# cape.net
KiCad netlist of a schematic drawn in EAGLE
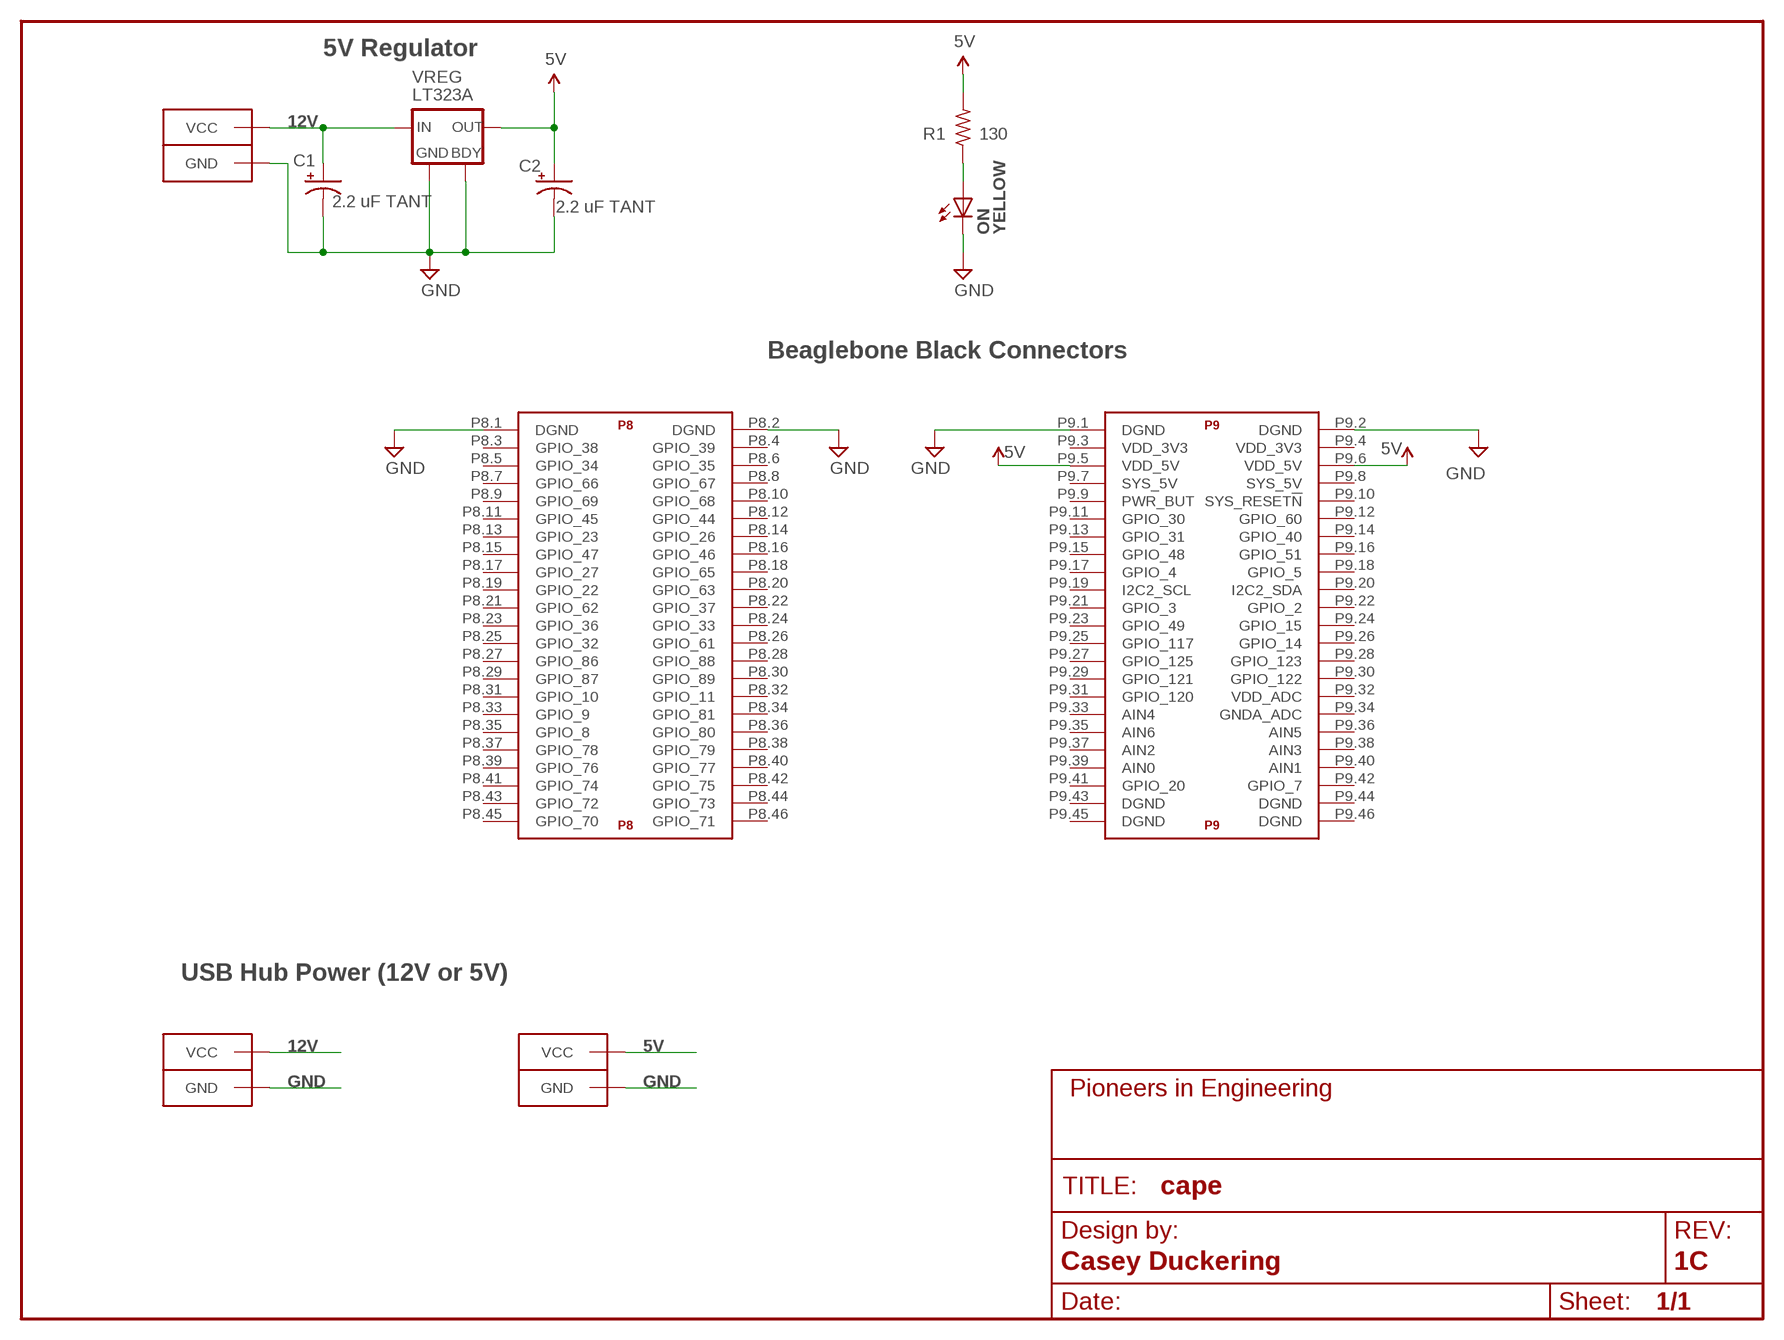
[diagram p0: schematic, sheet 1]

(export (version "E")
  (design (tool "Eeschema 10.0.6"))
  (components
    (comp (ref "BATT")
      (value "12V")
      (footprint "eagle-import:ANDERSON_HORIZONTAL")
      (libsource (lib "eagle-import") (part "ANDERSONHORIZONTAL"))
    )
    (comp (ref "C1")
      (value "2.2 uF TANT")
      (footprint "eagle-import:EIA3216")
      (libsource (lib "eagle-import") (part "CAP_POL1206"))
    )
    (comp (ref "C2")
      (value "2.2 uF TANT")
      (footprint "eagle-import:EIA3216")
      (libsource (lib "eagle-import") (part "CAP_POL1206"))
    )
    (comp (ref "CAPE")
      (value "BEAGLE_BONE_BLACK_CAPE")
      (footprint "eagle-import:BEAGLE_BONE_BLACK_CAPE")
      (libsource (lib "eagle-import") (part "BEAGLE_BONE_BLACK_CAPE"))
    )
    (comp (ref "J2")
      (value "12V")
      (footprint "eagle-import:POWER-WIRE")
      (libsource (lib "eagle-import") (part "POWER-WIRE"))
    )
    (comp (ref "J3")
      (value "5V")
      (footprint "eagle-import:POWER-WIRE")
      (libsource (lib "eagle-import") (part "POWER-WIRE"))
    )
    (comp (ref "ON")
      (value "YELLOW")
      (footprint "eagle-import:LED-0805")
      (libsource (lib "eagle-import") (part "LED0805"))
    )
    (comp (ref "R1")
      (value "130")
      (footprint "eagle-import:R0603")
      (libsource (lib "eagle-import") (part "R-US_R0603"))
    )
    (comp (ref "VREG")
      (value "LT323A")
      (footprint "eagle-import:TO-220")
      (libsource (lib "eagle-import") (part "V_REG_LT323A"))
    )
  )
  (nets
    (net (code "1") (name "/12V") (class "Default")
      (node (ref "BATT") (pin "PIN2") (pinfunction "VCC_PIN2") (pintype "bidirectional"))
      (node (ref "BATT") (pin "PIN2-LEAD") (pinfunction "VCC_PIN2-LEAD") (pintype "bidirectional"))
      (node (ref "C1") (pin "A") (pinfunction "+_A") (pintype "passive"))
      (node (ref "J2") (pin "VCC") (pinfunction "VCC_VCC") (pintype "bidirectional"))
      (node (ref "VREG") (pin "IN") (pinfunction "IN_IN") (pintype "input"))
    )
    (net (code "2") (name "5V") (class "Default")
      (node (ref "C2") (pin "A") (pinfunction "+_A") (pintype "passive"))
      (node (ref "CAPE") (pin "P9.5") (pinfunction "VDD_5V_P9.5") (pintype "bidirectional"))
      (node (ref "CAPE") (pin "P9.6") (pinfunction "VDD_5V_P9.6") (pintype "bidirectional"))
      (node (ref "J3") (pin "VCC") (pinfunction "VCC_VCC") (pintype "bidirectional"))
      (node (ref "R1") (pin "2") (pinfunction "2_2") (pintype "passive"))
      (node (ref "VREG") (pin "OUT") (pinfunction "OUT_OUT") (pintype "output"))
    )
    (net (code "3") (name "GND") (class "Default")
      (node (ref "BATT") (pin "PIN1") (pinfunction "GND_PIN1") (pintype "bidirectional"))
      (node (ref "BATT") (pin "PIN1-LEAD") (pinfunction "GND_PIN1-LEAD") (pintype "bidirectional"))
      (node (ref "C1") (pin "C") (pinfunction "-_C") (pintype "passive"))
      (node (ref "C2") (pin "C") (pinfunction "-_C") (pintype "passive"))
      (node (ref "CAPE") (pin "P8.1") (pinfunction "DGND_P8.1") (pintype "bidirectional"))
      (node (ref "CAPE") (pin "P8.2") (pinfunction "DGND_P8.2") (pintype "bidirectional"))
      (node (ref "CAPE") (pin "P9.1") (pinfunction "DGND_P9.1") (pintype "bidirectional"))
      (node (ref "CAPE") (pin "P9.2") (pinfunction "DGND_P9.2") (pintype "bidirectional"))
      (node (ref "J2") (pin "GND") (pinfunction "GND_GND") (pintype "bidirectional"))
      (node (ref "J3") (pin "GND") (pinfunction "GND_GND") (pintype "bidirectional"))
      (node (ref "ON") (pin "C") (pinfunction "C_C") (pintype "passive"))
      (node (ref "VREG") (pin "GND") (pinfunction "GND_GND") (pintype "input"))
      (node (ref "VREG") (pin "PAD") (pinfunction "BDY_PAD") (pintype "input"))
    )
    (net (code "4") (name "Net-(ON-PadA)") (class "Default")
      (node (ref "ON") (pin "A") (pinfunction "A_A") (pintype "passive"))
      (node (ref "R1") (pin "1") (pinfunction "1_1") (pintype "passive"))
    )
    (net (code "5") (name "unconnected-(CAPEA-GPIO_8-PadP8.35)") (class "Default")
      (node (ref "CAPE") (pin "P8.35") (pinfunction "GPIO_8_P8.35") (pintype "bidirectional"))
    )
    (net (code "6") (name "unconnected-(CAPEA-GPIO_9-PadP8.33)") (class "Default")
      (node (ref "CAPE") (pin "P8.33") (pinfunction "GPIO_9_P8.33") (pintype "bidirectional"))
    )
    (net (code "7") (name "unconnected-(CAPEA-GPIO_10-PadP8.31)") (class "Default")
      (node (ref "CAPE") (pin "P8.31") (pinfunction "GPIO_10_P8.31") (pintype "bidirectional"))
    )
    (net (code "8") (name "unconnected-(CAPEA-GPIO_11-PadP8.32)") (class "Default")
      (node (ref "CAPE") (pin "P8.32") (pinfunction "GPIO_11_P8.32") (pintype "bidirectional"))
    )
    (net (code "9") (name "unconnected-(CAPEA-GPIO_22-PadP8.19)") (class "Default")
      (node (ref "CAPE") (pin "P8.19") (pinfunction "GPIO_22_P8.19") (pintype "bidirectional"))
    )
    (net (code "10") (name "unconnected-(CAPEA-GPIO_23-PadP8.13)") (class "Default")
      (node (ref "CAPE") (pin "P8.13") (pinfunction "GPIO_23_P8.13") (pintype "bidirectional"))
    )
    (net (code "11") (name "unconnected-(CAPEA-GPIO_26-PadP8.14)") (class "Default")
      (node (ref "CAPE") (pin "P8.14") (pinfunction "GPIO_26_P8.14") (pintype "bidirectional"))
    )
    (net (code "12") (name "unconnected-(CAPEA-GPIO_27-PadP8.17)") (class "Default")
      (node (ref "CAPE") (pin "P8.17") (pinfunction "GPIO_27_P8.17") (pintype "bidirectional"))
    )
    (net (code "13") (name "unconnected-(CAPEA-GPIO_32-PadP8.25)") (class "Default")
      (node (ref "CAPE") (pin "P8.25") (pinfunction "GPIO_32_P8.25") (pintype "bidirectional"))
    )
    (net (code "14") (name "unconnected-(CAPEA-GPIO_33-PadP8.24)") (class "Default")
      (node (ref "CAPE") (pin "P8.24") (pinfunction "GPIO_33_P8.24") (pintype "bidirectional"))
    )
    (net (code "15") (name "unconnected-(CAPEA-GPIO_34-PadP8.5)") (class "Default")
      (node (ref "CAPE") (pin "P8.5") (pinfunction "GPIO_34_P8.5") (pintype "bidirectional"))
    )
    (net (code "16") (name "unconnected-(CAPEA-GPIO_35-PadP8.6)") (class "Default")
      (node (ref "CAPE") (pin "P8.6") (pinfunction "GPIO_35_P8.6") (pintype "bidirectional"))
    )
    (net (code "17") (name "unconnected-(CAPEA-GPIO_36-PadP8.23)") (class "Default")
      (node (ref "CAPE") (pin "P8.23") (pinfunction "GPIO_36_P8.23") (pintype "bidirectional"))
    )
    (net (code "18") (name "unconnected-(CAPEA-GPIO_37-PadP8.22)") (class "Default")
      (node (ref "CAPE") (pin "P8.22") (pinfunction "GPIO_37_P8.22") (pintype "bidirectional"))
    )
    (net (code "19") (name "unconnected-(CAPEA-GPIO_38-PadP8.3)") (class "Default")
      (node (ref "CAPE") (pin "P8.3") (pinfunction "GPIO_38_P8.3") (pintype "bidirectional"))
    )
    (net (code "20") (name "unconnected-(CAPEA-GPIO_39-PadP8.4)") (class "Default")
      (node (ref "CAPE") (pin "P8.4") (pinfunction "GPIO_39_P8.4") (pintype "bidirectional"))
    )
    (net (code "21") (name "unconnected-(CAPEA-GPIO_44-PadP8.12)") (class "Default")
      (node (ref "CAPE") (pin "P8.12") (pinfunction "GPIO_44_P8.12") (pintype "bidirectional"))
    )
    (net (code "22") (name "unconnected-(CAPEA-GPIO_45-PadP8.11)") (class "Default")
      (node (ref "CAPE") (pin "P8.11") (pinfunction "GPIO_45_P8.11") (pintype "bidirectional"))
    )
    (net (code "23") (name "unconnected-(CAPEA-GPIO_46-PadP8.16)") (class "Default")
      (node (ref "CAPE") (pin "P8.16") (pinfunction "GPIO_46_P8.16") (pintype "bidirectional"))
    )
    (net (code "24") (name "unconnected-(CAPEA-GPIO_47-PadP8.15)") (class "Default")
      (node (ref "CAPE") (pin "P8.15") (pinfunction "GPIO_47_P8.15") (pintype "bidirectional"))
    )
    (net (code "25") (name "unconnected-(CAPEA-GPIO_61-PadP8.26)") (class "Default")
      (node (ref "CAPE") (pin "P8.26") (pinfunction "GPIO_61_P8.26") (pintype "bidirectional"))
    )
    (net (code "26") (name "unconnected-(CAPEA-GPIO_62-PadP8.21)") (class "Default")
      (node (ref "CAPE") (pin "P8.21") (pinfunction "GPIO_62_P8.21") (pintype "bidirectional"))
    )
    (net (code "27") (name "unconnected-(CAPEA-GPIO_63-PadP8.20)") (class "Default")
      (node (ref "CAPE") (pin "P8.20") (pinfunction "GPIO_63_P8.20") (pintype "bidirectional"))
    )
    (net (code "28") (name "unconnected-(CAPEA-GPIO_65-PadP8.18)") (class "Default")
      (node (ref "CAPE") (pin "P8.18") (pinfunction "GPIO_65_P8.18") (pintype "bidirectional"))
    )
    (net (code "29") (name "unconnected-(CAPEA-GPIO_66-PadP8.7)") (class "Default")
      (node (ref "CAPE") (pin "P8.7") (pinfunction "GPIO_66_P8.7") (pintype "bidirectional"))
    )
    (net (code "30") (name "unconnected-(CAPEA-GPIO_67-PadP8.8)") (class "Default")
      (node (ref "CAPE") (pin "P8.8") (pinfunction "GPIO_67_P8.8") (pintype "bidirectional"))
    )
    (net (code "31") (name "unconnected-(CAPEA-GPIO_68-PadP8.10)") (class "Default")
      (node (ref "CAPE") (pin "P8.10") (pinfunction "GPIO_68_P8.10") (pintype "bidirectional"))
    )
    (net (code "32") (name "unconnected-(CAPEA-GPIO_69-PadP8.9)") (class "Default")
      (node (ref "CAPE") (pin "P8.9") (pinfunction "GPIO_69_P8.9") (pintype "bidirectional"))
    )
    (net (code "33") (name "unconnected-(CAPEA-GPIO_70-PadP8.45)") (class "Default")
      (node (ref "CAPE") (pin "P8.45") (pinfunction "GPIO_70_P8.45") (pintype "bidirectional"))
    )
    (net (code "34") (name "unconnected-(CAPEA-GPIO_71-PadP8.46)") (class "Default")
      (node (ref "CAPE") (pin "P8.46") (pinfunction "GPIO_71_P8.46") (pintype "bidirectional"))
    )
    (net (code "35") (name "unconnected-(CAPEA-GPIO_72-PadP8.43)") (class "Default")
      (node (ref "CAPE") (pin "P8.43") (pinfunction "GPIO_72_P8.43") (pintype "bidirectional"))
    )
    (net (code "36") (name "unconnected-(CAPEA-GPIO_73-PadP8.44)") (class "Default")
      (node (ref "CAPE") (pin "P8.44") (pinfunction "GPIO_73_P8.44") (pintype "bidirectional"))
    )
    (net (code "37") (name "unconnected-(CAPEA-GPIO_74-PadP8.41)") (class "Default")
      (node (ref "CAPE") (pin "P8.41") (pinfunction "GPIO_74_P8.41") (pintype "bidirectional"))
    )
    (net (code "38") (name "unconnected-(CAPEA-GPIO_75-PadP8.42)") (class "Default")
      (node (ref "CAPE") (pin "P8.42") (pinfunction "GPIO_75_P8.42") (pintype "bidirectional"))
    )
    (net (code "39") (name "unconnected-(CAPEA-GPIO_76-PadP8.39)") (class "Default")
      (node (ref "CAPE") (pin "P8.39") (pinfunction "GPIO_76_P8.39") (pintype "bidirectional"))
    )
    (net (code "40") (name "unconnected-(CAPEA-GPIO_77-PadP8.40)") (class "Default")
      (node (ref "CAPE") (pin "P8.40") (pinfunction "GPIO_77_P8.40") (pintype "bidirectional"))
    )
    (net (code "41") (name "unconnected-(CAPEA-GPIO_78-PadP8.37)") (class "Default")
      (node (ref "CAPE") (pin "P8.37") (pinfunction "GPIO_78_P8.37") (pintype "bidirectional"))
    )
    (net (code "42") (name "unconnected-(CAPEA-GPIO_79-PadP8.38)") (class "Default")
      (node (ref "CAPE") (pin "P8.38") (pinfunction "GPIO_79_P8.38") (pintype "bidirectional"))
    )
    (net (code "43") (name "unconnected-(CAPEA-GPIO_80-PadP8.36)") (class "Default")
      (node (ref "CAPE") (pin "P8.36") (pinfunction "GPIO_80_P8.36") (pintype "bidirectional"))
    )
    (net (code "44") (name "unconnected-(CAPEA-GPIO_81-PadP8.34)") (class "Default")
      (node (ref "CAPE") (pin "P8.34") (pinfunction "GPIO_81_P8.34") (pintype "bidirectional"))
    )
    (net (code "45") (name "unconnected-(CAPEA-GPIO_86-PadP8.27)") (class "Default")
      (node (ref "CAPE") (pin "P8.27") (pinfunction "GPIO_86_P8.27") (pintype "bidirectional"))
    )
    (net (code "46") (name "unconnected-(CAPEA-GPIO_87-PadP8.29)") (class "Default")
      (node (ref "CAPE") (pin "P8.29") (pinfunction "GPIO_87_P8.29") (pintype "bidirectional"))
    )
    (net (code "47") (name "unconnected-(CAPEA-GPIO_88-PadP8.28)") (class "Default")
      (node (ref "CAPE") (pin "P8.28") (pinfunction "GPIO_88_P8.28") (pintype "bidirectional"))
    )
    (net (code "48") (name "unconnected-(CAPEA-GPIO_89-PadP8.30)") (class "Default")
      (node (ref "CAPE") (pin "P8.30") (pinfunction "GPIO_89_P8.30") (pintype "bidirectional"))
    )
    (net (code "49") (name "unconnected-(CAPEB-AIN0-PadP9.39)") (class "Default")
      (node (ref "CAPE") (pin "P9.39") (pinfunction "AIN0_P9.39") (pintype "bidirectional"))
    )
    (net (code "50") (name "unconnected-(CAPEB-AIN1-PadP9.40)") (class "Default")
      (node (ref "CAPE") (pin "P9.40") (pinfunction "AIN1_P9.40") (pintype "bidirectional"))
    )
    (net (code "51") (name "unconnected-(CAPEB-AIN2-PadP9.37)") (class "Default")
      (node (ref "CAPE") (pin "P9.37") (pinfunction "AIN2_P9.37") (pintype "bidirectional"))
    )
    (net (code "52") (name "unconnected-(CAPEB-AIN3-PadP9.38)") (class "Default")
      (node (ref "CAPE") (pin "P9.38") (pinfunction "AIN3_P9.38") (pintype "bidirectional"))
    )
    (net (code "53") (name "unconnected-(CAPEB-AIN4-PadP9.33)") (class "Default")
      (node (ref "CAPE") (pin "P9.33") (pinfunction "AIN4_P9.33") (pintype "bidirectional"))
    )
    (net (code "54") (name "unconnected-(CAPEB-AIN5-PadP9.36)") (class "Default")
      (node (ref "CAPE") (pin "P9.36") (pinfunction "AIN5_P9.36") (pintype "bidirectional"))
    )
    (net (code "55") (name "unconnected-(CAPEB-AIN6-PadP9.35)") (class "Default")
      (node (ref "CAPE") (pin "P9.35") (pinfunction "AIN6_P9.35") (pintype "bidirectional"))
    )
    (net (code "56") (name "unconnected-(CAPEB-DGND-PadP9.43)") (class "Default")
      (node (ref "CAPE") (pin "P9.43") (pinfunction "DGND_P9.43") (pintype "bidirectional"))
    )
    (net (code "57") (name "unconnected-(CAPEB-DGND-PadP9.44)") (class "Default")
      (node (ref "CAPE") (pin "P9.44") (pinfunction "DGND_P9.44") (pintype "bidirectional"))
    )
    (net (code "58") (name "unconnected-(CAPEB-DGND-PadP9.45)") (class "Default")
      (node (ref "CAPE") (pin "P9.45") (pinfunction "DGND_P9.45") (pintype "bidirectional"))
    )
    (net (code "59") (name "unconnected-(CAPEB-DGND-PadP9.46)") (class "Default")
      (node (ref "CAPE") (pin "P9.46") (pinfunction "DGND_P9.46") (pintype "bidirectional"))
    )
    (net (code "60") (name "unconnected-(CAPEB-GNDA_ADC-PadP9.34)") (class "Default")
      (node (ref "CAPE") (pin "P9.34") (pinfunction "GNDA_ADC_P9.34") (pintype "bidirectional"))
    )
    (net (code "61") (name "unconnected-(CAPEB-GPIO_2-PadP9.22)") (class "Default")
      (node (ref "CAPE") (pin "P9.22") (pinfunction "GPIO_2_P9.22") (pintype "bidirectional"))
    )
    (net (code "62") (name "unconnected-(CAPEB-GPIO_3-PadP9.21)") (class "Default")
      (node (ref "CAPE") (pin "P9.21") (pinfunction "GPIO_3_P9.21") (pintype "bidirectional"))
    )
    (net (code "63") (name "unconnected-(CAPEB-GPIO_4-PadP9.17)") (class "Default")
      (node (ref "CAPE") (pin "P9.17") (pinfunction "GPIO_4_P9.17") (pintype "bidirectional"))
    )
    (net (code "64") (name "unconnected-(CAPEB-GPIO_5-PadP9.18)") (class "Default")
      (node (ref "CAPE") (pin "P9.18") (pinfunction "GPIO_5_P9.18") (pintype "bidirectional"))
    )
    (net (code "65") (name "unconnected-(CAPEB-GPIO_7-PadP9.42)") (class "Default")
      (node (ref "CAPE") (pin "P9.42") (pinfunction "GPIO_7_P9.42") (pintype "bidirectional"))
    )
    (net (code "66") (name "unconnected-(CAPEB-GPIO_14-PadP9.26)") (class "Default")
      (node (ref "CAPE") (pin "P9.26") (pinfunction "GPIO_14_P9.26") (pintype "bidirectional"))
    )
    (net (code "67") (name "unconnected-(CAPEB-GPIO_15-PadP9.24)") (class "Default")
      (node (ref "CAPE") (pin "P9.24") (pinfunction "GPIO_15_P9.24") (pintype "bidirectional"))
    )
    (net (code "68") (name "unconnected-(CAPEB-GPIO_20-PadP9.41)") (class "Default")
      (node (ref "CAPE") (pin "P9.41") (pinfunction "GPIO_20_P9.41") (pintype "bidirectional"))
    )
    (net (code "69") (name "unconnected-(CAPEB-GPIO_30-PadP9.11)") (class "Default")
      (node (ref "CAPE") (pin "P9.11") (pinfunction "GPIO_30_P9.11") (pintype "bidirectional"))
    )
    (net (code "70") (name "unconnected-(CAPEB-GPIO_31-PadP9.13)") (class "Default")
      (node (ref "CAPE") (pin "P9.13") (pinfunction "GPIO_31_P9.13") (pintype "bidirectional"))
    )
    (net (code "71") (name "unconnected-(CAPEB-GPIO_40-PadP9.14)") (class "Default")
      (node (ref "CAPE") (pin "P9.14") (pinfunction "GPIO_40_P9.14") (pintype "bidirectional"))
    )
    (net (code "72") (name "unconnected-(CAPEB-GPIO_48-PadP9.15)") (class "Default")
      (node (ref "CAPE") (pin "P9.15") (pinfunction "GPIO_48_P9.15") (pintype "bidirectional"))
    )
    (net (code "73") (name "unconnected-(CAPEB-GPIO_49-PadP9.23)") (class "Default")
      (node (ref "CAPE") (pin "P9.23") (pinfunction "GPIO_49_P9.23") (pintype "bidirectional"))
    )
    (net (code "74") (name "unconnected-(CAPEB-GPIO_51-PadP9.16)") (class "Default")
      (node (ref "CAPE") (pin "P9.16") (pinfunction "GPIO_51_P9.16") (pintype "bidirectional"))
    )
    (net (code "75") (name "unconnected-(CAPEB-GPIO_60-PadP9.12)") (class "Default")
      (node (ref "CAPE") (pin "P9.12") (pinfunction "GPIO_60_P9.12") (pintype "bidirectional"))
    )
    (net (code "76") (name "unconnected-(CAPEB-GPIO_117-PadP9.25)") (class "Default")
      (node (ref "CAPE") (pin "P9.25") (pinfunction "GPIO_117_P9.25") (pintype "bidirectional"))
    )
    (net (code "77") (name "unconnected-(CAPEB-GPIO_120-PadP9.31)") (class "Default")
      (node (ref "CAPE") (pin "P9.31") (pinfunction "GPIO_120_P9.31") (pintype "bidirectional"))
    )
    (net (code "78") (name "unconnected-(CAPEB-GPIO_121-PadP9.29)") (class "Default")
      (node (ref "CAPE") (pin "P9.29") (pinfunction "GPIO_121_P9.29") (pintype "bidirectional"))
    )
    (net (code "79") (name "unconnected-(CAPEB-GPIO_122-PadP9.30)") (class "Default")
      (node (ref "CAPE") (pin "P9.30") (pinfunction "GPIO_122_P9.30") (pintype "bidirectional"))
    )
    (net (code "80") (name "unconnected-(CAPEB-GPIO_123-PadP9.28)") (class "Default")
      (node (ref "CAPE") (pin "P9.28") (pinfunction "GPIO_123_P9.28") (pintype "bidirectional"))
    )
    (net (code "81") (name "unconnected-(CAPEB-GPIO_125-PadP9.27)") (class "Default")
      (node (ref "CAPE") (pin "P9.27") (pinfunction "GPIO_125_P9.27") (pintype "bidirectional"))
    )
    (net (code "82") (name "unconnected-(CAPEB-I2C2_SCL-PadP9.19)") (class "Default")
      (node (ref "CAPE") (pin "P9.19") (pinfunction "I2C2_SCL_P9.19") (pintype "bidirectional"))
    )
    (net (code "83") (name "unconnected-(CAPEB-I2C2_SDA-PadP9.20)") (class "Default")
      (node (ref "CAPE") (pin "P9.20") (pinfunction "I2C2_SDA_P9.20") (pintype "bidirectional"))
    )
    (net (code "84") (name "unconnected-(CAPEB-PWR_BUT-PadP9.9)") (class "Default")
      (node (ref "CAPE") (pin "P9.9") (pinfunction "PWR_BUT_P9.9") (pintype "bidirectional"))
    )
    (net (code "85") (name "unconnected-(CAPEB-SYS_5V-PadP9.7)") (class "Default")
      (node (ref "CAPE") (pin "P9.7") (pinfunction "SYS_5V_P9.7") (pintype "bidirectional"))
    )
    (net (code "86") (name "unconnected-(CAPEB-SYS_5V-PadP9.8)") (class "Default")
      (node (ref "CAPE") (pin "P9.8") (pinfunction "SYS_5V_P9.8") (pintype "bidirectional"))
    )
    (net (code "87") (name "unconnected-(CAPEB-SYS_RESET~{N}-PadP9.10)") (class "Default")
      (node (ref "CAPE") (pin "P9.10") (pinfunction "SYS_RESET~{N}_P9.10") (pintype "bidirectional"))
    )
    (net (code "88") (name "unconnected-(CAPEB-VDD_3V3-PadP9.3)") (class "Default")
      (node (ref "CAPE") (pin "P9.3") (pinfunction "VDD_3V3_P9.3") (pintype "bidirectional"))
    )
    (net (code "89") (name "unconnected-(CAPEB-VDD_3V3-PadP9.4)") (class "Default")
      (node (ref "CAPE") (pin "P9.4") (pinfunction "VDD_3V3_P9.4") (pintype "bidirectional"))
    )
    (net (code "90") (name "unconnected-(CAPEB-VDD_ADC-PadP9.32)") (class "Default")
      (node (ref "CAPE") (pin "P9.32") (pinfunction "VDD_ADC_P9.32") (pintype "bidirectional"))
    )
  )
)
